# Voltage_Divider.net
KiCad netlist of a schematic drawn in Altium Designer
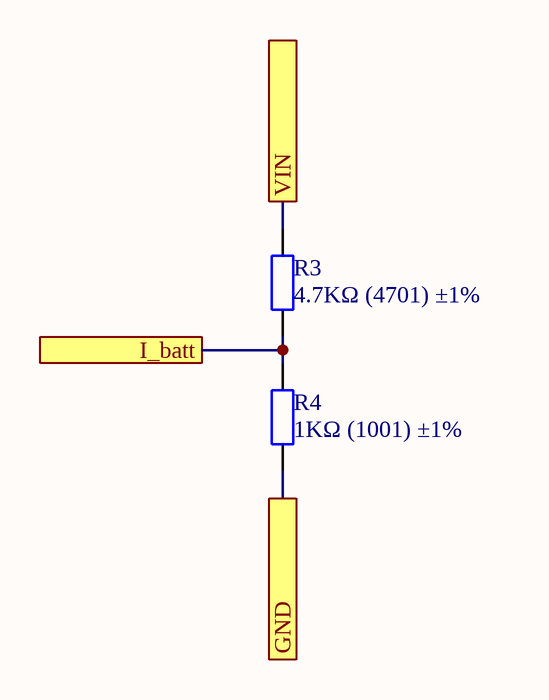
[diagram p0: Voltage_Divider.SchDoc]

(export (version "E")
  (design (tool "Eeschema 10.0.6"))
  (components
    (comp (ref "R3")
      (value "4.7KΩ (4701) ±1%")
      (footprint "0402_R")
      (description "贴片电阻")
      (libsource (lib "Miscellaneous Devices LC") (part "0402 4.7KΩ (4701) 1%"))
    )
    (comp (ref "R4")
      (value "1KΩ (1001) ±1%")
      (footprint "0402_R")
      (description "贴片电阻")
      (libsource (lib "Miscellaneous Devices LC") (part "0402 1KΩ (1001) 1%"))
    )
  )
  (nets
    (net (code "1") (name "/GND") (class "Default")
      (node (ref "R4") (pin "1") (pinfunction "1_1") (pintype "passive"))
    )
    (net (code "2") (name "/I_batt") (class "Default")
      (node (ref "R3") (pin "1") (pinfunction "1_1") (pintype "passive"))
      (node (ref "R4") (pin "2") (pinfunction "2_2") (pintype "passive"))
    )
    (net (code "3") (name "/VIN") (class "Default")
      (node (ref "R3") (pin "2") (pinfunction "2_2") (pintype "passive"))
    )
  )
)
